# ProDoc_Schematic_PCB_Shield_2026-03-18.net
KiCad netlist of a schematic drawn in EasyEDA Pro
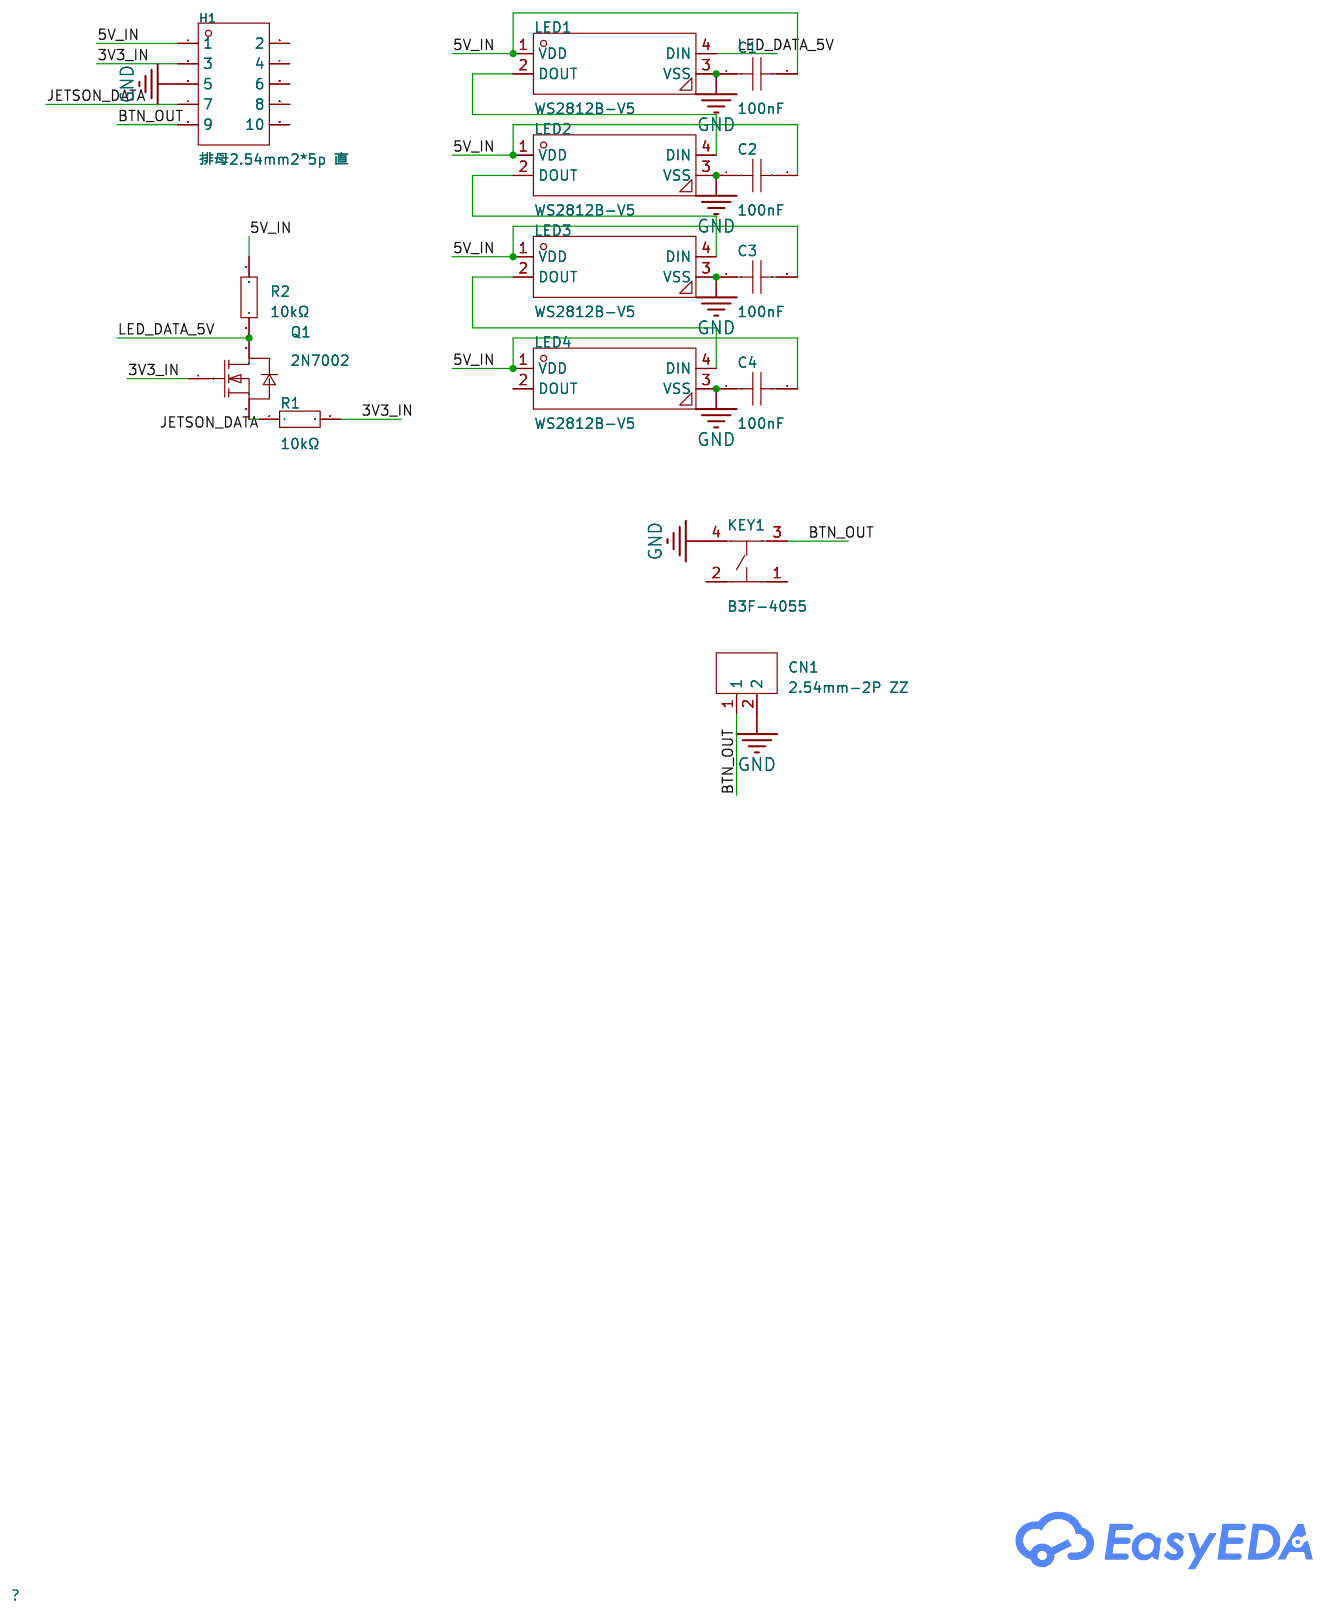
[diagram p0: schematic sheet]

(export (version "E")
  (design (tool "Eeschema 10.0.6"))
  (components
    (comp (ref "C1")
      (value "100nF")
      (footprint "easyedapro:C1812")
      (fields (field (name "Manufacturer Part") "SMDTC03100KB00KP00") (field (name "Manufacturer") "WIMA"))
      (libsource (lib "easyedapro") (part "SMDTC03100KB00KP00"))
    )
    (comp (ref "C2")
      (value "100nF")
      (footprint "easyedapro:C1812")
      (fields (field (name "Manufacturer Part") "SMDTC03100KB00KP00") (field (name "Manufacturer") "WIMA"))
      (libsource (lib "easyedapro") (part "SMDTC03100KB00KP00"))
    )
    (comp (ref "C3")
      (value "100nF")
      (footprint "easyedapro:C1812")
      (fields (field (name "Manufacturer Part") "SMDTC03100KB00KP00") (field (name "Manufacturer") "WIMA"))
      (libsource (lib "easyedapro") (part "SMDTC03100KB00KP00"))
    )
    (comp (ref "C4")
      (value "100nF")
      (footprint "easyedapro:C1812")
      (fields (field (name "Manufacturer Part") "SMDTC03100KB00KP00") (field (name "Manufacturer") "WIMA"))
      (libsource (lib "easyedapro") (part "SMDTC03100KB00KP00"))
    )
    (comp (ref "CN1")
      (value "2.54mm-2P ZZ")
      (footprint "easyedapro:CONN-TH_2.54MM-2P-ZZ")
      (fields (field (name "Manufacturer") "SHOU HAN(首韩)"))
      (libsource (lib "easyedapro") (part "2.54MM-2P ZZ"))
    )
    (comp (ref "H1")
      (value "排母2.54mm2*5p 直")
      (footprint "easyedapro:HDR-TH_10P-P2.54-V-F-R2-C5-S2.54")
      (fields (field (name "Manufacturer") "BOOMELE(博穆精密)"))
      (libsource (lib "easyedapro") (part "Female header2.54mm2*5p Straight"))
    )
    (comp (ref "KEY1")
      (value "B3F-4055")
      (footprint "easyedapro:KEY-TH_4P-L12.0-W12.0-P5.00-LS13.4-EH")
      (fields (field (name "Manufacturer") "OMRON(欧姆龙)"))
      (libsource (lib "easyedapro") (part "B3F-4055"))
    )
    (comp (ref "LED1")
      (value "WS2812B-V5")
      (footprint "easyedapro:LED-SMD_4P-L5.0-W5.0-LS5.4-TL-1")
      (fields (field (name "Manufacturer") "worldsemi"))
      (libsource (lib "easyedapro") (part "WS2812B-V5_C2846931"))
    )
    (comp (ref "LED2")
      (value "WS2812B-V5")
      (footprint "easyedapro:LED-SMD_4P-L5.0-W5.0-LS5.4-TL-1")
      (fields (field (name "Manufacturer") "worldsemi"))
      (libsource (lib "easyedapro") (part "WS2812B-V5_C2846931"))
    )
    (comp (ref "LED3")
      (value "WS2812B-V5")
      (footprint "easyedapro:LED-SMD_4P-L5.0-W5.0-LS5.4-TL-1")
      (fields (field (name "Manufacturer") "worldsemi"))
      (libsource (lib "easyedapro") (part "WS2812B-V5_C2846931"))
    )
    (comp (ref "LED4")
      (value "WS2812B-V5")
      (footprint "easyedapro:LED-SMD_4P-L5.0-W5.0-LS5.4-TL-1")
      (fields (field (name "Manufacturer") "worldsemi"))
      (libsource (lib "easyedapro") (part "WS2812B-V5_C2846931"))
    )
    (comp (ref "Q1")
      (value "2N7002")
      (footprint "easyedapro:SOT-23-3_L2.9-W1.3-P1.90-LS2.4-BR")
      (fields (field (name "Manufacturer") "CBI(创基)"))
      (libsource (lib "easyedapro") (part "2N7002_C51315010"))
    )
    (comp (ref "R1")
      (value "10kΩ")
      (footprint "easyedapro:RES-TH_BD1.8-L3.2-P7.20-D0.4")
      (fields (field (name "Manufacturer Part") "MF1/8W-10KΩ±1% T") (field (name "Manufacturer") "CCO(千志电子)"))
      (libsource (lib "easyedapro") (part "MF1/8W-10KΩ±1% T52"))
    )
    (comp (ref "R2")
      (value "10kΩ")
      (footprint "easyedapro:RES-TH_BD1.8-L3.2-P7.20-D0.4")
      (fields (field (name "Manufacturer Part") "MF1/8W-10KΩ±1% T") (field (name "Manufacturer") "CCO(千志电子)"))
      (libsource (lib "easyedapro") (part "MF1/8W-10KΩ±1% T52"))
    )
  )
  (nets
    (net (code "1") (name "/3V3_IN") (class "Default")
      (node (ref "H1") (pin "3") (pinfunction "3_3") (pintype "input"))
      (node (ref "Q1") (pin "1") (pinfunction "G_1") (pintype "unspecified"))
      (node (ref "R1") (pin "2") (pinfunction "2_2") (pintype "unspecified"))
    )
    (net (code "2") (name "/5V_IN") (class "Default")
      (node (ref "C1") (pin "2") (pinfunction "2_2") (pintype "unspecified"))
      (node (ref "C2") (pin "2") (pinfunction "2_2") (pintype "unspecified"))
      (node (ref "C3") (pin "2") (pinfunction "2_2") (pintype "unspecified"))
      (node (ref "C4") (pin "2") (pinfunction "2_2") (pintype "unspecified"))
      (node (ref "H1") (pin "1") (pinfunction "1_1") (pintype "input"))
      (node (ref "LED1") (pin "1") (pinfunction "VDD_1") (pintype "unspecified"))
      (node (ref "LED2") (pin "1") (pinfunction "VDD_1") (pintype "unspecified"))
      (node (ref "LED3") (pin "1") (pinfunction "VDD_1") (pintype "unspecified"))
      (node (ref "LED4") (pin "1") (pinfunction "VDD_1") (pintype "unspecified"))
      (node (ref "R2") (pin "2") (pinfunction "2_2") (pintype "unspecified"))
    )
    (net (code "3") (name "/BTN_OUT") (class "Default")
      (node (ref "CN1") (pin "1") (pinfunction "1_1") (pintype "unspecified"))
      (node (ref "H1") (pin "9") (pinfunction "9_9") (pintype "input"))
      (node (ref "KEY1") (pin "3") (pinfunction "3_3") (pintype "unspecified"))
    )
    (net (code "4") (name "/JETSON_DATA") (class "Default")
      (node (ref "H1") (pin "7") (pinfunction "7_7") (pintype "input"))
      (node (ref "Q1") (pin "2") (pinfunction "S_2") (pintype "unspecified"))
      (node (ref "R1") (pin "1") (pinfunction "1_1") (pintype "unspecified"))
    )
    (net (code "5") (name "/LED_DATA_5V") (class "Default")
      (node (ref "LED1") (pin "4") (pinfunction "DIN_4") (pintype "unspecified"))
      (node (ref "Q1") (pin "3") (pinfunction "D_3") (pintype "unspecified"))
      (node (ref "R2") (pin "1") (pinfunction "1_1") (pintype "unspecified"))
    )
    (net (code "6") (name "GND") (class "Default")
      (node (ref "C1") (pin "1") (pinfunction "1_1") (pintype "unspecified"))
      (node (ref "C2") (pin "1") (pinfunction "1_1") (pintype "unspecified"))
      (node (ref "C3") (pin "1") (pinfunction "1_1") (pintype "unspecified"))
      (node (ref "C4") (pin "1") (pinfunction "1_1") (pintype "unspecified"))
      (node (ref "CN1") (pin "2") (pinfunction "2_2") (pintype "unspecified"))
      (node (ref "H1") (pin "5") (pinfunction "5_5") (pintype "input"))
      (node (ref "KEY1") (pin "4") (pinfunction "4_4") (pintype "unspecified"))
      (node (ref "LED1") (pin "3") (pinfunction "VSS_3") (pintype "unspecified"))
      (node (ref "LED2") (pin "3") (pinfunction "VSS_3") (pintype "unspecified"))
      (node (ref "LED3") (pin "3") (pinfunction "VSS_3") (pintype "unspecified"))
      (node (ref "LED4") (pin "3") (pinfunction "VSS_3") (pintype "unspecified"))
    )
    (net (code "7") (name "Net-(LED1-DOUT)") (class "Default")
      (node (ref "LED1") (pin "2") (pinfunction "DOUT_2") (pintype "unspecified"))
      (node (ref "LED2") (pin "4") (pinfunction "DIN_4") (pintype "unspecified"))
    )
    (net (code "8") (name "Net-(LED2-DOUT)") (class "Default")
      (node (ref "LED2") (pin "2") (pinfunction "DOUT_2") (pintype "unspecified"))
      (node (ref "LED3") (pin "4") (pinfunction "DIN_4") (pintype "unspecified"))
    )
    (net (code "9") (name "Net-(LED3-DOUT)") (class "Default")
      (node (ref "LED3") (pin "2") (pinfunction "DOUT_2") (pintype "unspecified"))
      (node (ref "LED4") (pin "4") (pinfunction "DIN_4") (pintype "unspecified"))
    )
    (net (code "10") (name "unconnected-(H1-Pad2)") (class "Default")
      (node (ref "H1") (pin "2") (pinfunction "2_2") (pintype "input"))
    )
    (net (code "11") (name "unconnected-(H1-Pad4)") (class "Default")
      (node (ref "H1") (pin "4") (pinfunction "4_4") (pintype "input"))
    )
    (net (code "12") (name "unconnected-(H1-Pad6)") (class "Default")
      (node (ref "H1") (pin "6") (pinfunction "6_6") (pintype "input"))
    )
    (net (code "13") (name "unconnected-(H1-Pad8)") (class "Default")
      (node (ref "H1") (pin "8") (pinfunction "8_8") (pintype "input"))
    )
    (net (code "14") (name "unconnected-(H1-Pad10)") (class "Default")
      (node (ref "H1") (pin "10") (pinfunction "10_10") (pintype "input"))
    )
    (net (code "15") (name "unconnected-(KEY1-Pad1)") (class "Default")
      (node (ref "KEY1") (pin "1") (pinfunction "1_1") (pintype "unspecified"))
    )
    (net (code "16") (name "unconnected-(KEY1-Pad2)") (class "Default")
      (node (ref "KEY1") (pin "2") (pinfunction "2_2") (pintype "unspecified"))
    )
    (net (code "17") (name "unconnected-(LED4-DOUT-Pad2)") (class "Default")
      (node (ref "LED4") (pin "2") (pinfunction "DOUT_2") (pintype "unspecified"))
    )
  )
)
